# Polarshield_v2_3.net
KiCad netlist of a schematic drawn in EAGLE
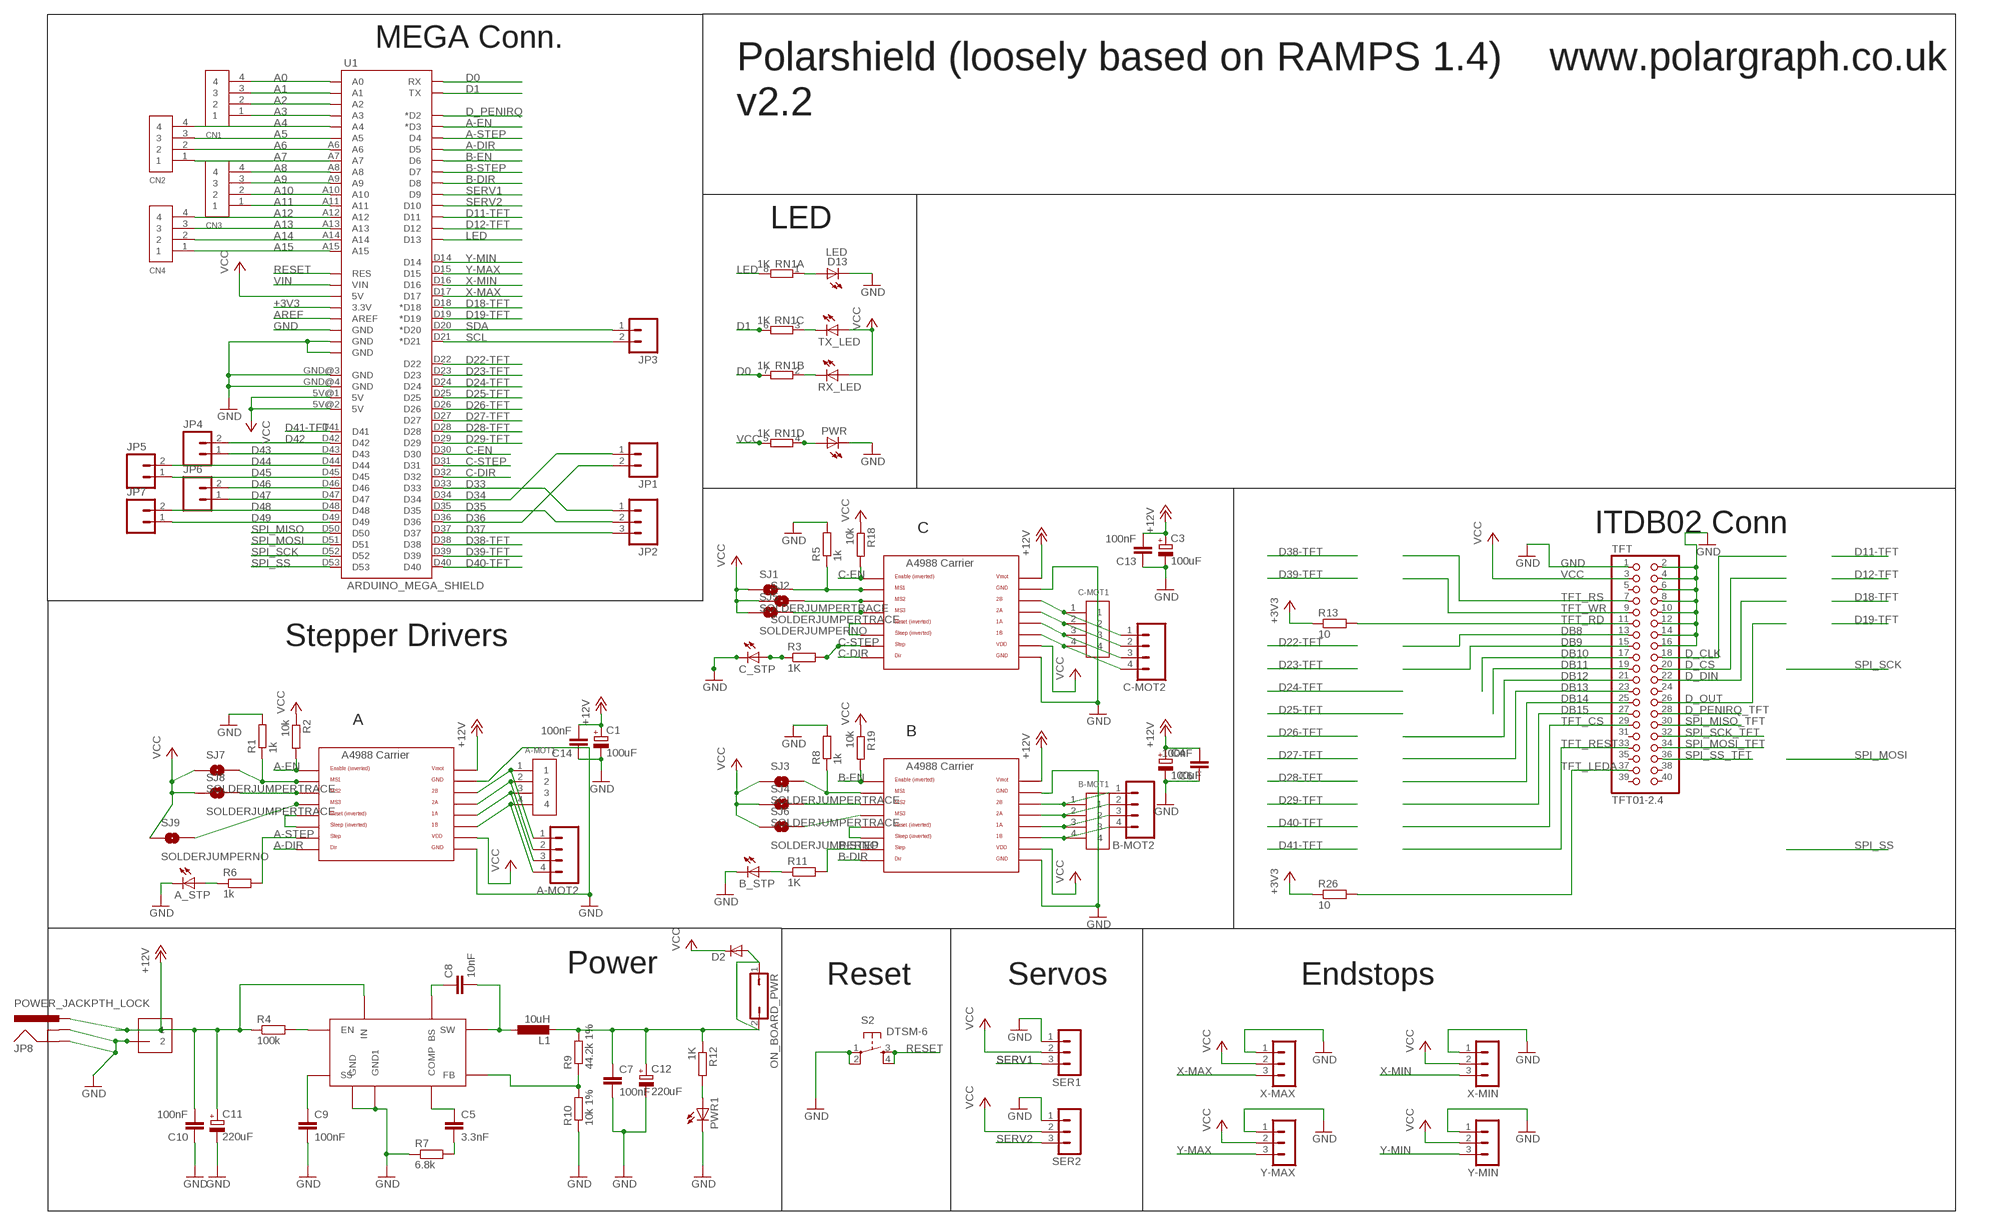
[diagram p0: schematic, sheet 1, part 1 of 2]
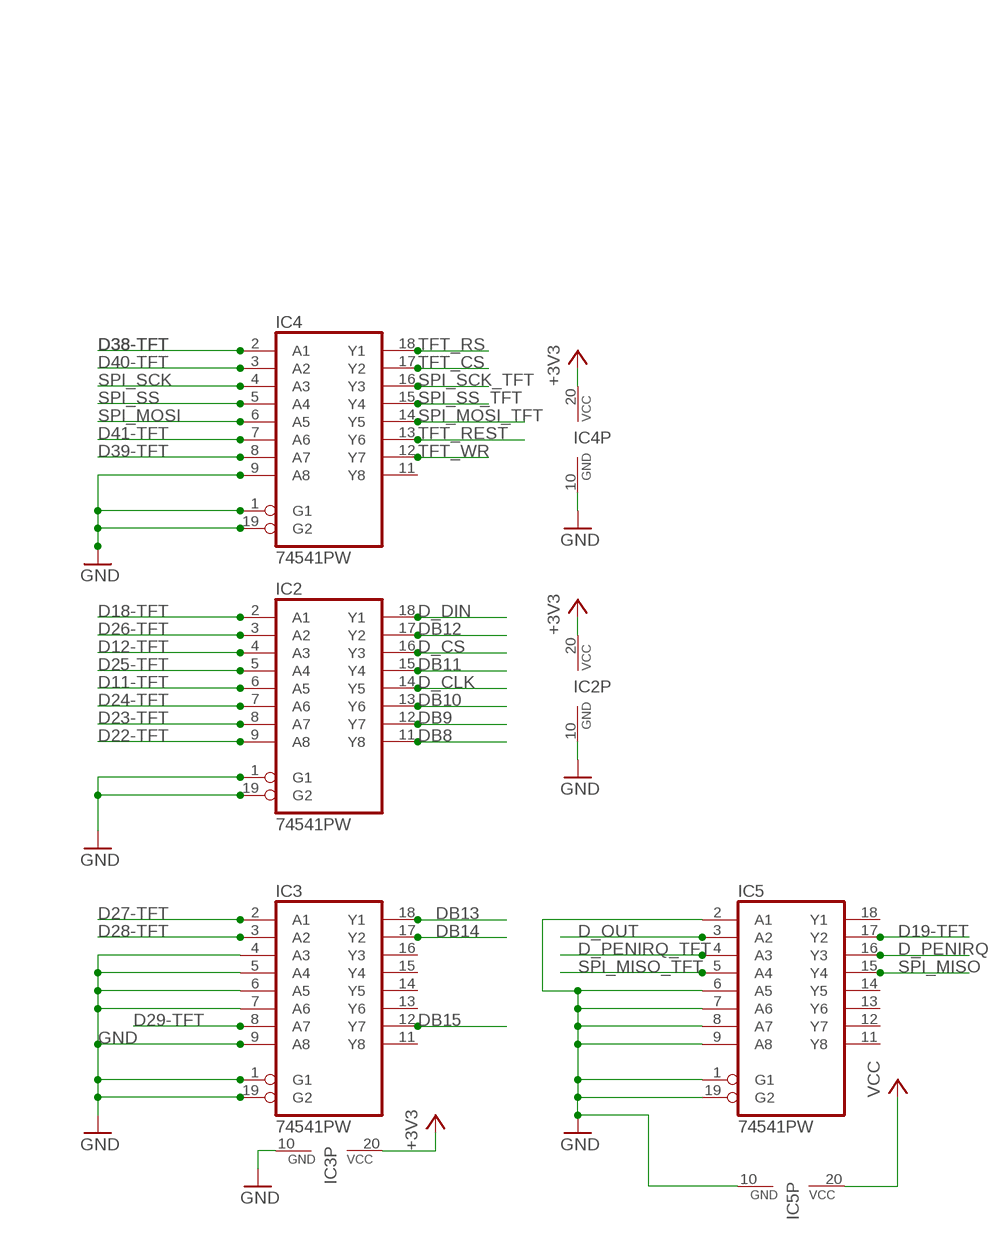
[diagram p1: schematic, sheet 1, part 2 of 2]

(export (version "E")
  (design (tool "Eeschema 10.0.6"))
  (components
    (comp (ref "A-MOT1")
      (value "1X4-BIG")
      (footprint "eagle-import:1X04-BIG")
      (libsource (lib "eagle-import") (part "adafruit_1X4-BIG"))
    )
    (comp (ref "A-MOT2")
      (value "M04SCREW")
      (footprint "eagle-import:SCREWTERMINAL-3.5MM-4")
      (libsource (lib "eagle-import") (part "M04SCREW"))
    )
    (comp (ref "A_STP")
      (value "LEDCHIP-LED0805")
      (footprint "eagle-import:CHIP-LED0805")
      (libsource (lib "eagle-import") (part "LEDCHIP-LED0805"))
    )
    (comp (ref "B-MOT1")
      (value "1X4-BIG")
      (footprint "eagle-import:1X04-BIG")
      (libsource (lib "eagle-import") (part "adafruit_1X4-BIG"))
    )
    (comp (ref "B-MOT2")
      (value "M04SCREW")
      (footprint "eagle-import:SCREWTERMINAL-3.5MM-4")
      (libsource (lib "eagle-import") (part "M04SCREW"))
    )
    (comp (ref "B_STP")
      (value "LEDCHIP-LED0805")
      (footprint "eagle-import:CHIP-LED0805")
      (libsource (lib "eagle-import") (part "LEDCHIP-LED0805"))
    )
    (comp (ref "C-MOT1")
      (value "1X4-BIG")
      (footprint "eagle-import:1X04-BIG")
      (libsource (lib "eagle-import") (part "adafruit_1X4-BIG"))
    )
    (comp (ref "C-MOT2")
      (value "M04SCREW")
      (footprint "eagle-import:SCREWTERMINAL-3.5MM-4")
      (libsource (lib "eagle-import") (part "M04SCREW"))
    )
    (comp (ref "C1")
      (value "100uF")
      (footprint "eagle-import:153CLV-0605")
      (libsource (lib "eagle-import") (part "CPOL-EU153CLV-0605"))
    )
    (comp (ref "C3")
      (value "100uF")
      (footprint "eagle-import:153CLV-0605")
      (libsource (lib "eagle-import") (part "CPOL-EU153CLV-0605"))
    )
    (comp (ref "C4")
      (value "100uF")
      (footprint "eagle-import:153CLV-0605")
      (libsource (lib "eagle-import") (part "CPOL-EU153CLV-0605"))
    )
    (comp (ref "C5")
      (value "3.3nF")
      (footprint "eagle-import:C0805K")
      (libsource (lib "eagle-import") (part "C-EUC0805K"))
    )
    (comp (ref "C6")
      (value "100nF")
      (footprint "eagle-import:C0805")
      (libsource (lib "eagle-import") (part "C-EUC0805"))
    )
    (comp (ref "C7")
      (value "100nF")
      (footprint "eagle-import:C0805K")
      (libsource (lib "eagle-import") (part "C-EUC0805K"))
    )
    (comp (ref "C8")
      (value "10nF")
      (footprint "eagle-import:C0805K")
      (libsource (lib "eagle-import") (part "C-EUC0805K"))
    )
    (comp (ref "C9")
      (value "100nF")
      (footprint "eagle-import:C0805K")
      (libsource (lib "eagle-import") (part "C-EUC0805K"))
    )
    (comp (ref "C10")
      (value "100nF")
      (footprint "eagle-import:C0805K")
      (libsource (lib "eagle-import") (part "C-EUC0805K"))
    )
    (comp (ref "C11")
      (value "220uF")
      (footprint "eagle-import:153CLV-0807")
      (libsource (lib "eagle-import") (part "resistor_CPOL-EU153CLV-0807"))
    )
    (comp (ref "C12")
      (value "220uF")
      (footprint "eagle-import:153CLV-0807")
      (libsource (lib "eagle-import") (part "resistor_CPOL-EU153CLV-0807"))
    )
    (comp (ref "C13")
      (value "100nF")
      (footprint "eagle-import:C0805")
      (libsource (lib "eagle-import") (part "C-EUC0805"))
    )
    (comp (ref "C14")
      (value "100nF")
      (footprint "eagle-import:C0805")
      (libsource (lib "eagle-import") (part "C-EUC0805"))
    )
    (comp (ref "CN1")
      (value "1X4-CLEANBIG")
      (footprint "eagle-import:1X04-CLEANBIG")
      (libsource (lib "eagle-import") (part "1X4-CLEANBIG"))
    )
    (comp (ref "CN2")
      (value "1X4-CLEANBIG")
      (footprint "eagle-import:1X04-CLEANBIG")
      (libsource (lib "eagle-import") (part "1X4-CLEANBIG"))
    )
    (comp (ref "CN3")
      (value "1X4-CLEANBIG")
      (footprint "eagle-import:1X04-CLEANBIG")
      (libsource (lib "eagle-import") (part "1X4-CLEANBIG"))
    )
    (comp (ref "CN4")
      (value "1X4-CLEANBIG")
      (footprint "eagle-import:1X04-CLEANBIG")
      (libsource (lib "eagle-import") (part "1X4-CLEANBIG"))
    )
    (comp (ref "C_STP")
      (value "LEDCHIP-LED0805")
      (footprint "eagle-import:CHIP-LED0805")
      (libsource (lib "eagle-import") (part "LEDCHIP-LED0805"))
    )
    (comp (ref "D2")
      (value "DIODE-DO214BA")
      (footprint "eagle-import:DO214BA")
      (libsource (lib "eagle-import") (part "DIODE-DO214BA"))
    )
    (comp (ref "D13")
      (value "LED")
      (footprint "eagle-import:CHIP-LED0805")
      (libsource (lib "eagle-import") (part "LEDCHIP-LED0805"))
    )
    (comp (ref "IC1")
      (value "MP2307")
      (footprint "eagle-import:SOIC8")
      (libsource (lib "eagle-import") (part "MP2307"))
    )
    (comp (ref "IC2")
      (value "74541PW")
      (footprint "eagle-import:TSSOP20")
      (libsource (lib "eagle-import") (part "74541PW"))
    )
    (comp (ref "IC3")
      (value "74541PW")
      (footprint "eagle-import:TSSOP20")
      (libsource (lib "eagle-import") (part "74541PW"))
    )
    (comp (ref "IC4")
      (value "74541PW")
      (footprint "eagle-import:TSSOP20")
      (libsource (lib "eagle-import") (part "74541PW"))
    )
    (comp (ref "IC5")
      (value "74541PW")
      (footprint "eagle-import:TSSOP20")
      (libsource (lib "eagle-import") (part "74541PW"))
    )
    (comp (ref "J1")
      (value "1X2-3.5MM")
      (footprint "eagle-import:1X2-3.5MM")
      (libsource (lib "eagle-import") (part "1X2-3.5MM"))
    )
    (comp (ref "JP1")
      (value "M021X02_NO_SILK")
      (footprint "eagle-import:1X02_NO_SILK")
      (libsource (lib "eagle-import") (part "M021X02_NO_SILK"))
    )
    (comp (ref "JP2")
      (value "M031X03_NO_SILK")
      (footprint "eagle-import:1X03_NO_SILK")
      (libsource (lib "eagle-import") (part "M031X03_NO_SILK"))
    )
    (comp (ref "JP3")
      (value "M021X02_NO_SILK")
      (footprint "eagle-import:1X02_NO_SILK")
      (libsource (lib "eagle-import") (part "M021X02_NO_SILK"))
    )
    (comp (ref "JP4")
      (value "M021X02_NO_SILK")
      (footprint "eagle-import:1X02_NO_SILK")
      (libsource (lib "eagle-import") (part "M021X02_NO_SILK"))
    )
    (comp (ref "JP5")
      (value "M021X02_NO_SILK")
      (footprint "eagle-import:1X02_NO_SILK")
      (libsource (lib "eagle-import") (part "M021X02_NO_SILK"))
    )
    (comp (ref "JP6")
      (value "M021X02_NO_SILK")
      (footprint "eagle-import:1X02_NO_SILK")
      (libsource (lib "eagle-import") (part "M021X02_NO_SILK"))
    )
    (comp (ref "JP7")
      (value "M021X02_NO_SILK")
      (footprint "eagle-import:1X02_NO_SILK")
      (libsource (lib "eagle-import") (part "M021X02_NO_SILK"))
    )
    (comp (ref "JP8")
      (value "POWER_JACKPTH_LOCK")
      (footprint "eagle-import:POWER_JACK_PTH_LOCK")
      (libsource (lib "eagle-import") (part "POWER_JACKPTH_LOCK"))
    )
    (comp (ref "L1")
      (value "10uH")
      (footprint "eagle-import:PIS2816")
      (libsource (lib "eagle-import") (part "L-EUPIS2816"))
    )
    (comp (ref "ON_BOARD_PWR")
      (value "JP1Q")
      (footprint "eagle-import:JP1")
      (libsource (lib "eagle-import") (part "JP1Q"))
    )
    (comp (ref "PWR")
      (value "LEDCHIP-LED0805")
      (footprint "eagle-import:CHIP-LED0805")
      (libsource (lib "eagle-import") (part "LEDCHIP-LED0805"))
    )
    (comp (ref "PWR1")
      (value "LEDCHIP-LED0805")
      (footprint "eagle-import:CHIP-LED0805")
      (libsource (lib "eagle-import") (part "LEDCHIP-LED0805"))
    )
    (comp (ref "R1")
      (value "1k")
      (footprint "eagle-import:R0805")
      (libsource (lib "eagle-import") (part "R-EU_R0805"))
    )
    (comp (ref "R2")
      (value "10k")
      (footprint "eagle-import:R0805")
      (libsource (lib "eagle-import") (part "R-EU_R0805"))
    )
    (comp (ref "R3")
      (value "1K")
      (footprint "eagle-import:R0805")
      (libsource (lib "eagle-import") (part "R-EU_R0805"))
    )
    (comp (ref "R4")
      (value "100k")
      (footprint "eagle-import:R0805")
      (libsource (lib "eagle-import") (part "resistor_R-EU_R0805"))
    )
    (comp (ref "R5")
      (value "1k")
      (footprint "eagle-import:R0805")
      (libsource (lib "eagle-import") (part "R-EU_R0805"))
    )
    (comp (ref "R6")
      (value "1k")
      (footprint "eagle-import:R0805")
      (libsource (lib "eagle-import") (part "R-EU_R0805"))
    )
    (comp (ref "R7")
      (value "6.8k")
      (footprint "eagle-import:R0805")
      (libsource (lib "eagle-import") (part "resistor_R-EU_R0805"))
    )
    (comp (ref "R8")
      (value "1k")
      (footprint "eagle-import:R0805")
      (libsource (lib "eagle-import") (part "R-EU_R0805"))
    )
    (comp (ref "R9")
      (value "44.2k 1%")
      (footprint "eagle-import:R0805")
      (libsource (lib "eagle-import") (part "resistor_R-EU_R0805"))
    )
    (comp (ref "R10")
      (value "10k 1%")
      (footprint "eagle-import:R0805")
      (libsource (lib "eagle-import") (part "resistor_R-EU_R0805"))
    )
    (comp (ref "R11")
      (value "1K")
      (footprint "eagle-import:R0805")
      (libsource (lib "eagle-import") (part "R-EU_R0805"))
    )
    (comp (ref "R12")
      (value "1K")
      (footprint "eagle-import:R0805")
      (libsource (lib "eagle-import") (part "R-EU_R0805"))
    )
    (comp (ref "R13")
      (value "10")
      (footprint "eagle-import:R0805")
      (libsource (lib "eagle-import") (part "resistor_R-EU_R0805"))
    )
    (comp (ref "R18")
      (value "10k")
      (footprint "eagle-import:R0805")
      (libsource (lib "eagle-import") (part "R-EU_R0805"))
    )
    (comp (ref "R19")
      (value "10k")
      (footprint "eagle-import:R0805")
      (libsource (lib "eagle-import") (part "R-EU_R0805"))
    )
    (comp (ref "R26")
      (value "10")
      (footprint "eagle-import:R0805")
      (libsource (lib "eagle-import") (part "resistor_R-EU_R0805"))
    )
    (comp (ref "RN1")
      (value "1K")
      (footprint "eagle-import:EXBS8V")
      (libsource (lib "eagle-import") (part "4R-NEXBS8V"))
    )
    (comp (ref "RX_LED")
      (value "LEDCHIP-LED0805")
      (footprint "eagle-import:CHIP-LED0805")
      (libsource (lib "eagle-import") (part "LEDCHIP-LED0805"))
    )
    (comp (ref "S2")
      (value "DTSM-6")
      (footprint "eagle-import:DTSM-6")
      (libsource (lib "eagle-import") (part "DTSM-6"))
    )
    (comp (ref "SER1")
      (value "3PIN-HEADER")
      (footprint "eagle-import:3PIN-HEADER")
      (libsource (lib "eagle-import") (part "3PIN-HEADER"))
    )
    (comp (ref "SER2")
      (value "3PIN-HEADER")
      (footprint "eagle-import:3PIN-HEADER")
      (libsource (lib "eagle-import") (part "3PIN-HEADER"))
    )
    (comp (ref "SJ1")
      (value "SOLDERJUMPERTRACE")
      (footprint "eagle-import:SJ_2S-TRACE")
      (libsource (lib "eagle-import") (part "SOLDERJUMPERTRACE"))
    )
    (comp (ref "SJ2")
      (value "SOLDERJUMPERTRACE")
      (footprint "eagle-import:SJ_2S-TRACE")
      (libsource (lib "eagle-import") (part "SOLDERJUMPERTRACE"))
    )
    (comp (ref "SJ3")
      (value "SOLDERJUMPERTRACE")
      (footprint "eagle-import:SJ_2S-TRACE")
      (libsource (lib "eagle-import") (part "SOLDERJUMPERTRACE"))
    )
    (comp (ref "SJ4")
      (value "SOLDERJUMPERTRACE")
      (footprint "eagle-import:SJ_2S-TRACE")
      (libsource (lib "eagle-import") (part "SOLDERJUMPERTRACE"))
    )
    (comp (ref "SJ5")
      (value "SOLDERJUMPERNO")
      (footprint "eagle-import:SJ_2S-NO")
      (libsource (lib "eagle-import") (part "SOLDERJUMPERNO"))
    )
    (comp (ref "SJ6")
      (value "SOLDERJUMPERNO")
      (footprint "eagle-import:SJ_2S-NO")
      (libsource (lib "eagle-import") (part "SOLDERJUMPERNO"))
    )
    (comp (ref "SJ7")
      (value "SOLDERJUMPERTRACE")
      (footprint "eagle-import:SJ_2S-TRACE")
      (libsource (lib "eagle-import") (part "SOLDERJUMPERTRACE"))
    )
    (comp (ref "SJ8")
      (value "SOLDERJUMPERTRACE")
      (footprint "eagle-import:SJ_2S-TRACE")
      (libsource (lib "eagle-import") (part "SOLDERJUMPERTRACE"))
    )
    (comp (ref "SJ9")
      (value "SOLDERJUMPERNO")
      (footprint "eagle-import:SJ_2S-NO")
      (libsource (lib "eagle-import") (part "SOLDERJUMPERNO"))
    )
    (comp (ref "TFT")
      (value "TFT01-2.4")
      (footprint "eagle-import:TFT01-2.4")
      (libsource (lib "eagle-import") (part "TFT01-2.4"))
    )
    (comp (ref "TX_LED")
      (value "LEDCHIP-LED0805")
      (footprint "eagle-import:CHIP-LED0805")
      (libsource (lib "eagle-import") (part "LEDCHIP-LED0805"))
    )
    (comp (ref "U$1")
      (value "A4988BREAKOUT")
      (footprint "eagle-import:A4988BREAKOUT")
      (libsource (lib "eagle-import") (part "A4988BREAKOUT"))
    )
    (comp (ref "U$6")
      (value "A4988BREAKOUT")
      (footprint "eagle-import:A4988BREAKOUT")
      (libsource (lib "eagle-import") (part "A4988BREAKOUT"))
    )
    (comp (ref "U$7")
      (value "A4988BREAKOUT")
      (footprint "eagle-import:A4988BREAKOUT")
      (libsource (lib "eagle-import") (part "A4988BREAKOUT"))
    )
    (comp (ref "U1")
      (value "ARDUINO_MEGA_SHIELD")
      (footprint "eagle-import:ARDUINO_MEGA_SHIELD")
      (libsource (lib "eagle-import") (part "ARDUINO_MEGA_SHIELD"))
    )
    (comp (ref "X-MAX")
      (value "3PIN-HEADER")
      (footprint "eagle-import:3PIN-HEADER")
      (libsource (lib "eagle-import") (part "3PIN-HEADER"))
    )
    (comp (ref "X-MIN")
      (value "3PIN-HEADER")
      (footprint "eagle-import:3PIN-HEADER")
      (libsource (lib "eagle-import") (part "3PIN-HEADER"))
    )
    (comp (ref "Y-MAX")
      (value "3PIN-HEADER")
      (footprint "eagle-import:3PIN-HEADER")
      (libsource (lib "eagle-import") (part "3PIN-HEADER"))
    )
    (comp (ref "Y-MIN")
      (value "3PIN-HEADER")
      (footprint "eagle-import:3PIN-HEADER")
      (libsource (lib "eagle-import") (part "3PIN-HEADER"))
    )
  )
  (nets
    (net (code "1") (name "+3V3") (class "Default")
      (node (ref "IC2") (pin "20") (pinfunction "VCC_20") (pintype "power_in"))
      (node (ref "IC3") (pin "20") (pinfunction "VCC_20") (pintype "power_in"))
      (node (ref "IC4") (pin "20") (pinfunction "VCC_20") (pintype "power_in"))
      (node (ref "R13") (pin "1") (pinfunction "1_1") (pintype "passive"))
      (node (ref "R26") (pin "1") (pinfunction "1_1") (pintype "passive"))
      (node (ref "U1") (pin "3.3V") (pinfunction "3.3V_3.3V") (pintype "bidirectional"))
    )
    (net (code "2") (name "+12V") (class "Default")
      (node (ref "C1") (pin "+") (pinfunction "+_+") (pintype "passive"))
      (node (ref "C10") (pin "2") (pinfunction "2_2") (pintype "passive"))
      (node (ref "C11") (pin "+") (pinfunction "+_+") (pintype "passive"))
      (node (ref "C13") (pin "2") (pinfunction "2_2") (pintype "passive"))
      (node (ref "C14") (pin "2") (pinfunction "2_2") (pintype "passive"))
      (node (ref "C3") (pin "+") (pinfunction "+_+") (pintype "passive"))
      (node (ref "C4") (pin "+") (pinfunction "+_+") (pintype "passive"))
      (node (ref "C6") (pin "2") (pinfunction "2_2") (pintype "passive"))
      (node (ref "IC1") (pin "IN") (pinfunction "IN_IN") (pintype "bidirectional"))
      (node (ref "J1") (pin "1") (pinfunction "1_1") (pintype "passive"))
      (node (ref "JP8") (pin "PWR") (pinfunction "PWR_PWR") (pintype "bidirectional"))
      (node (ref "R4") (pin "1") (pinfunction "1_1") (pintype "passive"))
      (node (ref "U$1") (pin "VMOT") (pinfunction "VMOT_VMOT") (pintype "power_in"))
      (node (ref "U$6") (pin "VMOT") (pinfunction "VMOT_VMOT") (pintype "power_in"))
      (node (ref "U$7") (pin "VMOT") (pinfunction "VMOT_VMOT") (pintype "power_in"))
    )
    (net (code "3") (name "/A-DIR") (class "Default")
      (node (ref "U$1") (pin "DIR") (pinfunction "DIR_DIR") (pintype "input"))
      (node (ref "U1") (pin "D5") (pinfunction "D5_D5") (pintype "bidirectional"))
    )
    (net (code "4") (name "/A-EN") (class "Default")
      (node (ref "R2") (pin "2") (pinfunction "2_2") (pintype "passive"))
      (node (ref "U$1") (pin "EN") (pinfunction "EN_EN") (pintype "input"))
      (node (ref "U1") (pin "D3") (pinfunction "*D3_D3") (pintype "bidirectional"))
    )
    (net (code "5") (name "/A-STEP") (class "Default")
      (node (ref "R6") (pin "2") (pinfunction "2_2") (pintype "passive"))
      (node (ref "U$1") (pin "STEP") (pinfunction "STEP_STEP") (pintype "input"))
      (node (ref "U1") (pin "D4") (pinfunction "D4_D4") (pintype "bidirectional"))
    )
    (net (code "6") (name "/A0") (class "Default")
      (node (ref "CN1") (pin "4") (pinfunction "4_4") (pintype "bidirectional"))
      (node (ref "U1") (pin "A0") (pinfunction "A0_A0") (pintype "bidirectional"))
    )
    (net (code "7") (name "/A1") (class "Default")
      (node (ref "CN1") (pin "3") (pinfunction "3_3") (pintype "bidirectional"))
      (node (ref "U1") (pin "A1") (pinfunction "A1_A1") (pintype "bidirectional"))
    )
    (net (code "8") (name "/A2") (class "Default")
      (node (ref "CN1") (pin "2") (pinfunction "2_2") (pintype "bidirectional"))
      (node (ref "U1") (pin "A2") (pinfunction "A2_A2") (pintype "bidirectional"))
    )
    (net (code "9") (name "/A3") (class "Default")
      (node (ref "CN1") (pin "1") (pinfunction "1_1") (pintype "bidirectional"))
      (node (ref "U1") (pin "A3") (pinfunction "A3_A3") (pintype "bidirectional"))
    )
    (net (code "10") (name "/A4") (class "Default")
      (node (ref "CN2") (pin "4") (pinfunction "4_4") (pintype "bidirectional"))
      (node (ref "U1") (pin "A4") (pinfunction "A4_A4") (pintype "bidirectional"))
    )
    (net (code "11") (name "/A5") (class "Default")
      (node (ref "CN2") (pin "3") (pinfunction "3_3") (pintype "bidirectional"))
      (node (ref "U1") (pin "A5") (pinfunction "A5_A5") (pintype "bidirectional"))
    )
    (net (code "12") (name "/A6") (class "Default")
      (node (ref "CN2") (pin "2") (pinfunction "2_2") (pintype "bidirectional"))
      (node (ref "U1") (pin "A6") (pinfunction "A6_A6") (pintype "bidirectional"))
    )
    (net (code "13") (name "/A7") (class "Default")
      (node (ref "CN2") (pin "1") (pinfunction "1_1") (pintype "bidirectional"))
      (node (ref "U1") (pin "A7") (pinfunction "A7_A7") (pintype "bidirectional"))
    )
    (net (code "14") (name "/A8") (class "Default")
      (node (ref "CN3") (pin "4") (pinfunction "4_4") (pintype "bidirectional"))
      (node (ref "U1") (pin "A8") (pinfunction "A8_A8") (pintype "bidirectional"))
    )
    (net (code "15") (name "/A9") (class "Default")
      (node (ref "CN3") (pin "3") (pinfunction "3_3") (pintype "bidirectional"))
      (node (ref "U1") (pin "A9") (pinfunction "A9_A9") (pintype "bidirectional"))
    )
    (net (code "16") (name "/A10") (class "Default")
      (node (ref "CN3") (pin "2") (pinfunction "2_2") (pintype "bidirectional"))
      (node (ref "U1") (pin "A10") (pinfunction "A10_A10") (pintype "bidirectional"))
    )
    (net (code "17") (name "/A11") (class "Default")
      (node (ref "CN3") (pin "1") (pinfunction "1_1") (pintype "bidirectional"))
      (node (ref "U1") (pin "A11") (pinfunction "A11_A11") (pintype "bidirectional"))
    )
    (net (code "18") (name "/A12") (class "Default")
      (node (ref "CN4") (pin "4") (pinfunction "4_4") (pintype "bidirectional"))
      (node (ref "U1") (pin "A12") (pinfunction "A12_A12") (pintype "bidirectional"))
    )
    (net (code "19") (name "/A13") (class "Default")
      (node (ref "CN4") (pin "3") (pinfunction "3_3") (pintype "bidirectional"))
      (node (ref "U1") (pin "A13") (pinfunction "A13_A13") (pintype "bidirectional"))
    )
    (net (code "20") (name "/A14") (class "Default")
      (node (ref "CN4") (pin "2") (pinfunction "2_2") (pintype "bidirectional"))
      (node (ref "U1") (pin "A14") (pinfunction "A14_A14") (pintype "bidirectional"))
    )
    (net (code "21") (name "/A15") (class "Default")
      (node (ref "CN4") (pin "1") (pinfunction "1_1") (pintype "bidirectional"))
      (node (ref "U1") (pin "A15") (pinfunction "A15_A15") (pintype "bidirectional"))
    )
    (net (code "22") (name "/AREF") (class "Default")
      (node (ref "U1") (pin "AREF") (pinfunction "AREF_AREF") (pintype "bidirectional"))
    )
    (net (code "23") (name "/B-DIR") (class "Default")
      (node (ref "U$7") (pin "DIR") (pinfunction "DIR_DIR") (pintype "input"))
      (node (ref "U1") (pin "D8") (pinfunction "D8_D8") (pintype "bidirectional"))
    )
    (net (code "24") (name "/B-EN") (class "Default")
      (node (ref "R19") (pin "2") (pinfunction "2_2") (pintype "passive"))
      (node (ref "U$7") (pin "EN") (pinfunction "EN_EN") (pintype "input"))
      (node (ref "U1") (pin "D6") (pinfunction "D6_D6") (pintype "bidirectional"))
    )
    (net (code "25") (name "/B-STEP") (class "Default")
      (node (ref "R11") (pin "2") (pinfunction "2_2") (pintype "passive"))
      (node (ref "U$7") (pin "STEP") (pinfunction "STEP_STEP") (pintype "input"))
      (node (ref "U1") (pin "D7") (pinfunction "D7_D7") (pintype "bidirectional"))
    )
    (net (code "26") (name "/C-DIR") (class "Default")
      (node (ref "U$6") (pin "DIR") (pinfunction "DIR_DIR") (pintype "input"))
      (node (ref "U1") (pin "D32") (pinfunction "D32_D32") (pintype "bidirectional"))
    )
    (net (code "27") (name "/C-EN") (class "Default")
      (node (ref "R18") (pin "2") (pinfunction "2_2") (pintype "passive"))
      (node (ref "U$6") (pin "EN") (pinfunction "EN_EN") (pintype "input"))
      (node (ref "U1") (pin "D30") (pinfunction "D30_D30") (pintype "bidirectional"))
    )
    (net (code "28") (name "/C-STEP") (class "Default")
      (node (ref "R3") (pin "2") (pinfunction "2_2") (pintype "passive"))
      (node (ref "U$6") (pin "STEP") (pinfunction "STEP_STEP") (pintype "input"))
      (node (ref "U1") (pin "D31") (pinfunction "D31_D31") (pintype "bidirectional"))
    )
    (net (code "29") (name "/D0") (class "Default")
      (node (ref "RN1") (pin "7") (pinfunction "2_7") (pintype "passive"))
      (node (ref "U1") (pin "RX") (pinfunction "RX_RX") (pintype "bidirectional"))
    )
    (net (code "30") (name "/D1") (class "Default")
      (node (ref "RN1") (pin "6") (pinfunction "2_6") (pintype "passive"))
      (node (ref "U1") (pin "TX") (pinfunction "TX_TX") (pintype "bidirectional"))
    )
    (net (code "31") (name "/D11-TFT") (class "Default")
      (node (ref "IC2") (pin "6") (pinfunction "A5_6") (pintype "input"))
      (node (ref "U1") (pin "D11") (pinfunction "D11_D11") (pintype "bidirectional"))
    )
    (net (code "32") (name "/D12-TFT") (class "Default")
      (node (ref "IC2") (pin "4") (pinfunction "A3_4") (pintype "input"))
      (node (ref "U1") (pin "D12") (pinfunction "D12_D12") (pintype "bidirectional"))
    )
    (net (code "33") (name "/D18-TFT") (class "Default")
      (node (ref "IC2") (pin "2") (pinfunction "A1_2") (pintype "input"))
      (node (ref "U1") (pin "D18") (pinfunction "*D18_D18") (pintype "bidirectional"))
    )
    (net (code "34") (name "/D19-TFT") (class "Default")
      (node (ref "IC5") (pin "17") (pinfunction "Y2_17") (pintype "tri_state"))
      (node (ref "U1") (pin "D19") (pinfunction "*D19_D19") (pintype "bidirectional"))
    )
    (net (code "35") (name "/D22-TFT") (class "Default")
      (node (ref "IC2") (pin "9") (pinfunction "A8_9") (pintype "input"))
      (node (ref "U1") (pin "D22") (pinfunction "D22_D22") (pintype "bidirectional"))
    )
    (net (code "36") (name "/D23-TFT") (class "Default")
      (node (ref "IC2") (pin "8") (pinfunction "A7_8") (pintype "input"))
      (node (ref "U1") (pin "D23") (pinfunction "D23_D23") (pintype "bidirectional"))
    )
    (net (code "37") (name "/D24-TFT") (class "Default")
      (node (ref "IC2") (pin "7") (pinfunction "A6_7") (pintype "input"))
      (node (ref "U1") (pin "D24") (pinfunction "D24_D24") (pintype "bidirectional"))
    )
    (net (code "38") (name "/D25-TFT") (class "Default")
      (node (ref "IC2") (pin "5") (pinfunction "A4_5") (pintype "input"))
      (node (ref "U1") (pin "D25") (pinfunction "D25_D25") (pintype "bidirectional"))
    )
    (net (code "39") (name "/D26-TFT") (class "Default")
      (node (ref "IC2") (pin "3") (pinfunction "A2_3") (pintype "input"))
      (node (ref "U1") (pin "D26") (pinfunction "D26_D26") (pintype "bidirectional"))
    )
    (net (code "40") (name "/D27-TFT") (class "Default")
      (node (ref "IC3") (pin "2") (pinfunction "A1_2") (pintype "input"))
      (node (ref "U1") (pin "D27") (pinfunction "D27_D27") (pintype "bidirectional"))
    )
    (net (code "41") (name "/D28-TFT") (class "Default")
      (node (ref "IC3") (pin "3") (pinfunction "A2_3") (pintype "input"))
      (node (ref "U1") (pin "D28") (pinfunction "D28_D28") (pintype "bidirectional"))
    )
    (net (code "42") (name "/D29-TFT") (class "Default")
      (node (ref "IC3") (pin "8") (pinfunction "A7_8") (pintype "input"))
      (node (ref "U1") (pin "D29") (pinfunction "D29_D29") (pintype "bidirectional"))
    )
    (net (code "43") (name "/D33") (class "Default")
      (node (ref "JP2") (pin "1") (pinfunction "1_1") (pintype "passive"))
      (node (ref "U1") (pin "D33") (pinfunction "D33_D33") (pintype "bidirectional"))
    )
    (net (code "44") (name "/D34") (class "Default")
      (node (ref "JP1") (pin "1") (pinfunction "1_1") (pintype "passive"))
      (node (ref "U1") (pin "D34") (pinfunction "D34_D34") (pintype "bidirectional"))
    )
    (net (code "45") (name "/D35") (class "Default")
      (node (ref "JP2") (pin "2") (pinfunction "2_2") (pintype "passive"))
      (node (ref "U1") (pin "D35") (pinfunction "D35_D35") (pintype "bidirectional"))
    )
    (net (code "46") (name "/D36") (class "Default")
      (node (ref "JP1") (pin "2") (pinfunction "2_2") (pintype "passive"))
      (node (ref "U1") (pin "D36") (pinfunction "D36_D36") (pintype "bidirectional"))
    )
    (net (code "47") (name "/D37") (class "Default")
      (node (ref "JP2") (pin "3") (pinfunction "3_3") (pintype "passive"))
      (node (ref "U1") (pin "D37") (pinfunction "D37_D37") (pintype "bidirectional"))
    )
    (net (code "48") (name "/D38-TFT") (class "Default")
      (node (ref "IC4") (pin "2") (pinfunction "A1_2") (pintype "input"))
      (node (ref "U1") (pin "D38") (pinfunction "D38_D38") (pintype "bidirectional"))
    )
    (net (code "49") (name "/D39-TFT") (class "Default")
      (node (ref "IC4") (pin "8") (pinfunction "A7_8") (pintype "input"))
      (node (ref "U1") (pin "D39") (pinfunction "D39_D39") (pintype "bidirectional"))
    )
    (net (code "50") (name "/D40-TFT") (class "Default")
      (node (ref "IC4") (pin "3") (pinfunction "A2_3") (pintype "input"))
      (node (ref "U1") (pin "D40") (pinfunction "D40_D40") (pintype "bidirectional"))
    )
    (net (code "51") (name "/D41-TFT") (class "Default")
      (node (ref "IC4") (pin "7") (pinfunction "A6_7") (pintype "input"))
      (node (ref "U1") (pin "D41") (pinfunction "D41_D41") (pintype "bidirectional"))
    )
    (net (code "52") (name "/D42") (class "Default")
      (node (ref "JP4") (pin "2") (pinfunction "2_2") (pintype "passive"))
      (node (ref "U1") (pin "D42") (pinfunction "D42_D42") (pintype "bidirectional"))
    )
    (net (code "53") (name "/D43") (class "Default")
      (node (ref "JP4") (pin "1") (pinfunction "1_1") (pintype "passive"))
      (node (ref "U1") (pin "D43") (pinfunction "D43_D43") (pintype "bidirectional"))
    )
    (net (code "54") (name "/D44") (class "Default")
      (node (ref "JP5") (pin "2") (pinfunction "2_2") (pintype "passive"))
      (node (ref "U1") (pin "D44") (pinfunction "D44_D44") (pintype "bidirectional"))
    )
    (net (code "55") (name "/D45") (class "Default")
      (node (ref "JP5") (pin "1") (pinfunction "1_1") (pintype "passive"))
      (node (ref "U1") (pin "D45") (pinfunction "D45_D45") (pintype "bidirectional"))
    )
    (net (code "56") (name "/D46") (class "Default")
      (node (ref "JP6") (pin "2") (pinfunction "2_2") (pintype "passive"))
      (node (ref "U1") (pin "D46") (pinfunction "D46_D46") (pintype "bidirectional"))
    )
    (net (code "57") (name "/D47") (class "Default")
      (node (ref "JP6") (pin "1") (pinfunction "1_1") (pintype "passive"))
      (node (ref "U1") (pin "D47") (pinfunction "D47_D47") (pintype "bidirectional"))
    )
    (net (code "58") (name "/D48") (class "Default")
      (node (ref "JP7") (pin "2") (pinfunction "2_2") (pintype "passive"))
      (node (ref "U1") (pin "D48") (pinfunction "D48_D48") (pintype "bidirectional"))
    )
    (net (code "59") (name "/D49") (class "Default")
      (node (ref "JP7") (pin "1") (pinfunction "1_1") (pintype "passive"))
      (node (ref "U1") (pin "D49") (pinfunction "D49_D49") (pintype "bidirectional"))
    )
    (net (code "60") (name "/DB8") (class "Default")
      (node (ref "IC2") (pin "11") (pinfunction "Y8_11") (pintype "tri_state"))
      (node (ref "TFT") (pin "13") (pinfunction "13_13") (pintype "passive"))
    )
    (net (code "61") (name "/DB9") (class "Default")
      (node (ref "IC2") (pin "12") (pinfunction "Y7_12") (pintype "tri_state"))
      (node (ref "TFT") (pin "15") (pinfunction "15_15") (pintype "passive"))
    )
    (net (code "62") (name "/DB10") (class "Default")
      (node (ref "IC2") (pin "13") (pinfunction "Y6_13") (pintype "tri_state"))
      (node (ref "TFT") (pin "17") (pinfunction "17_17") (pintype "passive"))
    )
    (net (code "63") (name "/DB11") (class "Default")
      (node (ref "IC2") (pin "15") (pinfunction "Y4_15") (pintype "tri_state"))
      (node (ref "TFT") (pin "19") (pinfunction "19_19") (pintype "passive"))
    )
    (net (code "64") (name "/DB12") (class "Default")
      (node (ref "IC2") (pin "17") (pinfunction "Y2_17") (pintype "tri_state"))
      (node (ref "TFT") (pin "21") (pinfunction "21_21") (pintype "passive"))
    )
    (net (code "65") (name "/DB13") (class "Default")
      (node (ref "IC3") (pin "18") (pinfunction "Y1_18") (pintype "tri_state"))
      (node (ref "TFT") (pin "23") (pinfunction "23_23") (pintype "passive"))
    )
    (net (code "66") (name "/DB14") (class "Default")
      (node (ref "IC3") (pin "17") (pinfunction "Y2_17") (pintype "tri_state"))
      (node (ref "TFT") (pin "25") (pinfunction "25_25") (pintype "passive"))
    )
    (net (code "67") (name "/DB15") (class "Default")
      (node (ref "IC3") (pin "12") (pinfunction "Y7_12") (pintype "tri_state"))
      (node (ref "TFT") (pin "27") (pinfunction "27_27") (pintype "passive"))
    )
    (net (code "68") (name "/D_CLK") (class "Default")
      (node (ref "IC2") (pin "14") (pinfunction "Y5_14") (pintype "tri_state"))
      (node (ref "TFT") (pin "18") (pinfunction "18_18") (pintype "passive"))
    )
    (net (code "69") (name "/D_CS") (class "Default")
      (node (ref "IC2") (pin "16") (pinfunction "Y3_16") (pintype "tri_state"))
      (node (ref "TFT") (pin "20") (pinfunction "20_20") (pintype "passive"))
    )
    (net (code "70") (name "/D_DIN") (class "Default")
      (node (ref "IC2") (pin "18") (pinfunction "Y1_18") (pintype "tri_state"))
      (node (ref "TFT") (pin "22") (pinfunction "22_22") (pintype "passive"))
    )
    (net (code "71") (name "/D_OUT") (class "Default")
      (node (ref "IC5") (pin "3") (pinfunction "A2_3") (pintype "input"))
      (node (ref "TFT") (pin "26") (pinfunction "26_26") (pintype "passive"))
    )
    (net (code "72") (name "/D_PENIRQ") (class "Default")
      (node (ref "IC5") (pin "16") (pinfunction "Y3_16") (pintype "tri_state"))
      (node (ref "U1") (pin "D2") (pinfunction "*D2_D2") (pintype "bidirectional"))
    )
    (net (code "73") (name "/D_PENIRQ_TFT") (class "Default")
      (node (ref "IC5") (pin "4") (pinfunction "A3_4") (pintype "input"))
      (node (ref "TFT") (pin "28") (pinfunction "28_28") (pintype "passive"))
    )
    (net (code "74") (name "/LED") (class "Default")
      (node (ref "RN1") (pin "8") (pinfunction "2_8") (pintype "passive"))
      (node (ref "U1") (pin "D13") (pinfunction "D13_D13") (pintype "bidirectional"))
    )
    (net (code "75") (name "/RESET") (class "Default")
      (node (ref "S2") (pin "3") (pinfunction "3_3") (pintype "passive"))
      (node (ref "S2") (pin "4") (pinfunction "4_4") (pintype "passive"))
      (node (ref "U1") (pin "RES") (pinfunction "RES_RES") (pintype "bidirectional"))
    )
    (net (code "76") (name "/SCL") (class "Default")
      (node (ref "JP3") (pin "2") (pinfunction "2_2") (pintype "passive"))
      (node (ref "U1") (pin "D21") (pinfunction "*D21_D21") (pintype "bidirectional"))
    )
    (net (code "77") (name "/SDA") (class "Default")
      (node (ref "JP3") (pin "1") (pinfunction "1_1") (pintype "passive"))
      (node (ref "U1") (pin "D20") (pinfunction "*D20_D20") (pintype "bidirectional"))
    )
    (net (code "78") (name "/SERV1") (class "Default")
      (node (ref "SER1") (pin "3") (pinfunction "3_3") (pintype "passive"))
      (node (ref "U1") (pin "D9") (pinfunction "D9_D9") (pintype "bidirectional"))
    )
    (net (code "79") (name "/SERV2") (class "Default")
      (node (ref "SER2") (pin "3") (pinfunction "3_3") (pintype "passive"))
      (node (ref "U1") (pin "D10") (pinfunction "D10_D10") (pintype "bidirectional"))
    )
    (net (code "80") (name "/SPI_MISO") (class "Default")
      (node (ref "IC5") (pin "15") (pinfunction "Y4_15") (pintype "tri_state"))
      (node (ref "U1") (pin "D50") (pinfunction "D50_D50") (pintype "bidirectional"))
    )
    (net (code "81") (name "/SPI_MISO_TFT") (class "Default")
      (node (ref "IC5") (pin "5") (pinfunction "A4_5") (pintype "input"))
      (node (ref "TFT") (pin "30") (pinfunction "30_30") (pintype "passive"))
    )
    (net (code "82") (name "/SPI_MOSI") (class "Default")
      (node (ref "IC4") (pin "6") (pinfunction "A5_6") (pintype "input"))
      (node (ref "U1") (pin "D51") (pinfunction "D51_D51") (pintype "bidirectional"))
    )
    (net (code "83") (name "/SPI_MOSI_TFT") (class "Default")
      (node (ref "IC4") (pin "14") (pinfunction "Y5_14") (pintype "tri_state"))
      (node (ref "TFT") (pin "34") (pinfunction "34_34") (pintype "passive"))
    )
    (net (code "84") (name "/SPI_SCK") (class "Default")
      (node (ref "IC4") (pin "4") (pinfunction "A3_4") (pintype "input"))
      (node (ref "U1") (pin "D52") (pinfunction "D52_D52") (pintype "bidirectional"))
    )
    (net (code "85") (name "/SPI_SCK_TFT") (class "Default")
      (node (ref "IC4") (pin "16") (pinfunction "Y3_16") (pintype "tri_state"))
      (node (ref "TFT") (pin "32") (pinfunction "32_32") (pintype "passive"))
    )
    (net (code "86") (name "/SPI_SS") (class "Default")
      (node (ref "IC4") (pin "5") (pinfunction "A4_5") (pintype "input"))
      (node (ref "U1") (pin "D53") (pinfunction "D53_D53") (pintype "bidirectional"))
    )
    (net (code "87") (name "/SPI_SS_TFT") (class "Default")
      (node (ref "IC4") (pin "15") (pinfunction "Y4_15") (pintype "tri_state"))
      (node (ref "TFT") (pin "36") (pinfunction "36_36") (pintype "passive"))
    )
    (net (code "88") (name "/TFT_CS") (class "Default")
      (node (ref "IC4") (pin "17") (pinfunction "Y2_17") (pintype "tri_state"))
      (node (ref "TFT") (pin "29") (pinfunction "29_29") (pintype "passive"))
    )
    (net (code "89") (name "/TFT_LEDA") (class "Default")
      (node (ref "R26") (pin "2") (pinfunction "2_2") (pintype "passive"))
      (node (ref "TFT") (pin "37") (pinfunction "37_37") (pintype "passive"))
    )
    (net (code "90") (name "/TFT_RD") (class "Default")
      (node (ref "R13") (pin "2") (pinfunction "2_2") (pintype "passive"))
      (node (ref "TFT") (pin "11") (pinfunction "11_11") (pintype "passive"))
    )
    (net (code "91") (name "/TFT_REST") (class "Default")
      (node (ref "IC4") (pin "13") (pinfunction "Y6_13") (pintype "tri_state"))
      (node (ref "TFT") (pin "33") (pinfunction "33_33") (pintype "passive"))
    )
    (net (code "92") (name "/TFT_RS") (class "Default")
      (node (ref "IC4") (pin "18") (pinfunction "Y1_18") (pintype "tri_state"))
      (node (ref "TFT") (pin "7") (pinfunction "7_7") (pintype "passive"))
    )
    (net (code "93") (name "/TFT_WR") (class "Default")
      (node (ref "IC4") (pin "12") (pinfunction "Y7_12") (pintype "tri_state"))
      (node (ref "TFT") (pin "9") (pinfunction "9_9") (pintype "passive"))
    )
    (net (code "94") (name "/VIN") (class "Default")
      (node (ref "U1") (pin "VIN") (pinfunction "VIN_VIN") (pintype "bidirectional"))
    )
    (net (code "95") (name "/X-MAX") (class "Default")
      (node (ref "U1") (pin "D17") (pinfunction "D17_D17") (pintype "bidirectional"))
      (node (ref "X-MAX") (pin "3") (pinfunction "3_3") (pintype "passive"))
    )
    (net (code "96") (name "/X-MIN") (class "Default")
      (node (ref "U1") (pin "D16") (pinfunction "D16_D16") (pintype "bidirectional"))
      (node (ref "X-MIN") (pin "3") (pinfunction "3_3") (pintype "passive"))
    )
    (net (code "97") (name "/Y-MAX") (class "Default")
      (node (ref "U1") (pin "D15") (pinfunction "D15_D15") (pintype "bidirectional"))
      (node (ref "Y-MAX") (pin "3") (pinfunction "3_3") (pintype "passive"))
    )
    (net (code "98") (name "/Y-MIN") (class "Default")
      (node (ref "U1") (pin "D14") (pinfunction "D14_D14") (pintype "bidirectional"))
      (node (ref "Y-MIN") (pin "3") (pinfunction "3_3") (pintype "passive"))
    )
    (net (code "99") (name "GND") (class "Default")
      (node (ref "A_STP") (pin "C") (pinfunction "C_C") (pintype "passive"))
      (node (ref "B_STP") (pin "C") (pinfunction "C_C") (pintype "passive"))
      (node (ref "C1") (pin "-") (pinfunction "-_-") (pintype "passive"))
      (node (ref "C10") (pin "1") (pinfunction "1_1") (pintype "passive"))
      (node (ref "C11") (pin "-") (pinfunction "-_-") (pintype "passive"))
      (node (ref "C12") (pin "-") (pinfunction "-_-") (pintype "passive"))
      (node (ref "C13") (pin "1") (pinfunction "1_1") (pintype "passive"))
      (node (ref "C14") (pin "1") (pinfunction "1_1") (pintype "passive"))
      (node (ref "C3") (pin "-") (pinfunction "-_-") (pintype "passive"))
      (node (ref "C4") (pin "-") (pinfunction "-_-") (pintype "passive"))
      (node (ref "C6") (pin "1") (pinfunction "1_1") (pintype "passive"))
      (node (ref "C7") (pin "2") (pinfunction "2_2") (pintype "passive"))
      (node (ref "C9") (pin "2") (pinfunction "2_2") (pintype "passive"))
      (node (ref "C_STP") (pin "C") (pinfunction "C_C") (pintype "passive"))
      (node (ref "D13") (pin "C") (pinfunction "C_C") (pintype "passive"))
      (node (ref "IC1") (pin "GND") (pinfunction "GND_GND") (pintype "bidirectional"))
      (node (ref "IC1") (pin "GND1") (pinfunction "GND1_GND1") (pintype "bidirectional"))
      (node (ref "IC2") (pin "1") (pinfunction "G1_1") (pintype "input"))
      (node (ref "IC2") (pin "10") (pinfunction "GND_10") (pintype "power_in"))
      (node (ref "IC2") (pin "19") (pinfunction "G2_19") (pintype "input"))
      (node (ref "IC3") (pin "1") (pinfunction "G1_1") (pintype "input"))
      (node (ref "IC3") (pin "10") (pinfunction "GND_10") (pintype "power_in"))
      (node (ref "IC3") (pin "19") (pinfunction "G2_19") (pintype "input"))
      (node (ref "IC3") (pin "4") (pinfunction "A3_4") (pintype "input"))
      (node (ref "IC3") (pin "5") (pinfunction "A4_5") (pintype "input"))
      (node (ref "IC3") (pin "6") (pinfunction "A5_6") (pintype "input"))
      (node (ref "IC3") (pin "7") (pinfunction "A6_7") (pintype "input"))
      (node (ref "IC3") (pin "9") (pinfunction "A8_9") (pintype "input"))
      (node (ref "IC4") (pin "1") (pinfunction "G1_1") (pintype "input"))
      (node (ref "IC4") (pin "10") (pinfunction "GND_10") (pintype "power_in"))
      (node (ref "IC4") (pin "19") (pinfunction "G2_19") (pintype "input"))
      (node (ref "IC4") (pin "9") (pinfunction "A8_9") (pintype "input"))
      (node (ref "IC5") (pin "1") (pinfunction "G1_1") (pintype "input"))
      (node (ref "IC5") (pin "10") (pinfunction "GND_10") (pintype "power_in"))
      (node (ref "IC5") (pin "19") (pinfunction "G2_19") (pintype "input"))
      (node (ref "IC5") (pin "2") (pinfunction "A1_2") (pintype "input"))
      (node (ref "IC5") (pin "6") (pinfunction "A5_6") (pintype "input"))
      (node (ref "IC5") (pin "7") (pinfunction "A6_7") (pintype "input"))
      (node (ref "IC5") (pin "8") (pinfunction "A7_8") (pintype "input"))
      (node (ref "IC5") (pin "9") (pinfunction "A8_9") (pintype "input"))
      (node (ref "J1") (pin "2") (pinfunction "2_2") (pintype "passive"))
      (node (ref "JP8") (pin "GND") (pinfunction "GND_GND") (pintype "bidirectional"))
      (node (ref "JP8") (pin "GNDBREAK") (pinfunction "GNDBREAK_GNDBREAK") (pintype "bidirectional"))
      (node (ref "PWR") (pin "C") (pinfunction "C_C") (pintype "passive"))
      (node (ref "PWR1") (pin "C") (pinfunction "C_C") (pintype "passive"))
      (node (ref "R1") (pin "2") (pinfunction "2_2") (pintype "passive"))
      (node (ref "R10") (pin "1") (pinfunction "1_1") (pintype "passive"))
      (node (ref "R5") (pin "2") (pinfunction "2_2") (pintype "passive"))
      (node (ref "R7") (pin "1") (pinfunction "1_1") (pintype "passive"))
      (node (ref "R8") (pin "2") (pinfunction "2_2") (pintype "passive"))
      (node (ref "S2") (pin "1") (pinfunction "1_1") (pintype "passive"))
      (node (ref "S2") (pin "2") (pinfunction "2_2") (pintype "passive"))
      (node (ref "SER1") (pin "1") (pinfunction "1_1") (pintype "passive"))
      (node (ref "SER2") (pin "1") (pinfunction "1_1") (pintype "passive"))
      (node (ref "TFT") (pin "1") (pinfunction "1_1") (pintype "passive"))
      (node (ref "TFT") (pin "10") (pinfunction "10_10") (pintype "passive"))
      (node (ref "TFT") (pin "12") (pinfunction "12_12") (pintype "passive"))
      (node (ref "TFT") (pin "14") (pinfunction "14_14") (pintype "passive"))
      (node (ref "TFT") (pin "16") (pinfunction "16_16") (pintype "passive"))
      (node (ref "TFT") (pin "2") (pinfunction "2_2") (pintype "passive"))
      (node (ref "TFT") (pin "4") (pinfunction "4_4") (pintype "passive"))
      (node (ref "TFT") (pin "6") (pinfunction "6_6") (pintype "passive"))
      (node (ref "TFT") (pin "8") (pinfunction "8_8") (pintype "passive"))
      (node (ref "U$1") (pin "GND") (pinfunction "GND_GND") (pintype "power_in"))
      (node (ref "U$1") (pin "GND@0") (pinfunction "GND_GND@0") (pintype "power_in"))
      (node (ref "U$6") (pin "GND") (pinfunction "GND_GND") (pintype "power_in"))
      (node (ref "U$6") (pin "GND@0") (pinfunction "GND_GND@0") (pintype "power_in"))
      (node (ref "U$7") (pin "GND") (pinfunction "GND_GND") (pintype "power_in"))
      (node (ref "U$7") (pin "GND@0") (pinfunction "GND_GND@0") (pintype "power_in"))
      (node (ref "U1") (pin "GND@0") (pinfunction "GND_GND@0") (pintype "power_in"))
      (node (ref "U1") (pin "GND@1") (pinfunction "GND_GND@1") (pintype "power_in"))
      (node (ref "U1") (pin "GND@2") (pinfunction "GND_GND@2") (pintype "power_in"))
      (node (ref "U1") (pin "GND@3") (pinfunction "GND_GND@3") (pintype "power_in"))
      (node (ref "U1") (pin "GND@4") (pinfunction "GND_GND@4") (pintype "power_in"))
      (node (ref "X-MAX") (pin "1") (pinfunction "1_1") (pintype "passive"))
      (node (ref "X-MIN") (pin "1") (pinfunction "1_1") (pintype "passive"))
      (node (ref "Y-MAX") (pin "1") (pinfunction "1_1") (pintype "passive"))
      (node (ref "Y-MIN") (pin "1") (pinfunction "1_1") (pintype "passive"))
    )
    (net (code "100") (name "Net-(A-MOT1-Pad1)") (class "Default")
      (node (ref "A-MOT1") (pin "1") (pinfunction "1_1") (pintype "bidirectional"))
      (node (ref "A-MOT2") (pin "1") (pinfunction "1_1") (pintype "passive"))
      (node (ref "U$1") (pin "2B") (pinfunction "2B_2B") (pintype "output"))
    )
    (net (code "101") (name "Net-(A-MOT1-Pad2)") (class "Default")
      (node (ref "A-MOT1") (pin "2") (pinfunction "2_2") (pintype "bidirectional"))
      (node (ref "A-MOT2") (pin "2") (pinfunction "2_2") (pintype "passive"))
      (node (ref "U$1") (pin "2A") (pinfunction "2A_2A") (pintype "output"))
    )
    (net (code "102") (name "Net-(A-MOT1-Pad3)") (class "Default")
      (node (ref "A-MOT1") (pin "3") (pinfunction "3_3") (pintype "bidirectional"))
      (node (ref "A-MOT2") (pin "3") (pinfunction "3_3") (pintype "passive"))
      (node (ref "U$1") (pin "1A") (pinfunction "1A_1A") (pintype "output"))
    )
    (net (code "103") (name "Net-(A-MOT1-Pad4)") (class "Default")
      (node (ref "A-MOT1") (pin "4") (pinfunction "4_4") (pintype "bidirectional"))
      (node (ref "A-MOT2") (pin "4") (pinfunction "4_4") (pintype "passive"))
      (node (ref "U$1") (pin "1B") (pinfunction "1B_1B") (pintype "output"))
    )
    (net (code "104") (name "Net-(A_STP-PadA)") (class "Default")
      (node (ref "A_STP") (pin "A") (pinfunction "A_A") (pintype "passive"))
      (node (ref "R6") (pin "1") (pinfunction "1_1") (pintype "passive"))
    )
    (net (code "105") (name "Net-(B-MOT1-Pad1)") (class "Default")
      (node (ref "B-MOT1") (pin "1") (pinfunction "1_1") (pintype "bidirectional"))
      (node (ref "B-MOT2") (pin "1") (pinfunction "1_1") (pintype "passive"))
      (node (ref "U$7") (pin "2B") (pinfunction "2B_2B") (pintype "output"))
    )
    (net (code "106") (name "Net-(B-MOT1-Pad2)") (class "Default")
      (node (ref "B-MOT1") (pin "2") (pinfunction "2_2") (pintype "bidirectional"))
      (node (ref "B-MOT2") (pin "2") (pinfunction "2_2") (pintype "passive"))
      (node (ref "U$7") (pin "2A") (pinfunction "2A_2A") (pintype "output"))
    )
    (net (code "107") (name "Net-(B-MOT1-Pad3)") (class "Default")
      (node (ref "B-MOT1") (pin "3") (pinfunction "3_3") (pintype "bidirectional"))
      (node (ref "B-MOT2") (pin "3") (pinfunction "3_3") (pintype "passive"))
      (node (ref "U$7") (pin "1A") (pinfunction "1A_1A") (pintype "output"))
    )
    (net (code "108") (name "Net-(B-MOT1-Pad4)") (class "Default")
      (node (ref "B-MOT1") (pin "4") (pinfunction "4_4") (pintype "bidirectional"))
      (node (ref "B-MOT2") (pin "4") (pinfunction "4_4") (pintype "passive"))
      (node (ref "U$7") (pin "1B") (pinfunction "1B_1B") (pintype "output"))
    )
    (net (code "109") (name "Net-(B_STP-PadA)") (class "Default")
      (node (ref "B_STP") (pin "A") (pinfunction "A_A") (pintype "passive"))
      (node (ref "R11") (pin "1") (pinfunction "1_1") (pintype "passive"))
    )
    (net (code "110") (name "Net-(C-MOT1-Pad1)") (class "Default")
      (node (ref "C-MOT1") (pin "1") (pinfunction "1_1") (pintype "bidirectional"))
      (node (ref "C-MOT2") (pin "1") (pinfunction "1_1") (pintype "passive"))
      (node (ref "U$6") (pin "2B") (pinfunction "2B_2B") (pintype "output"))
    )
    (net (code "111") (name "Net-(C-MOT1-Pad2)") (class "Default")
      (node (ref "C-MOT1") (pin "2") (pinfunction "2_2") (pintype "bidirectional"))
      (node (ref "C-MOT2") (pin "2") (pinfunction "2_2") (pintype "passive"))
      (node (ref "U$6") (pin "2A") (pinfunction "2A_2A") (pintype "output"))
    )
    (net (code "112") (name "Net-(C-MOT1-Pad3)") (class "Default")
      (node (ref "C-MOT1") (pin "3") (pinfunction "3_3") (pintype "bidirectional"))
      (node (ref "C-MOT2") (pin "3") (pinfunction "3_3") (pintype "passive"))
      (node (ref "U$6") (pin "1A") (pinfunction "1A_1A") (pintype "output"))
    )
    (net (code "113") (name "Net-(C-MOT1-Pad4)") (class "Default")
      (node (ref "C-MOT1") (pin "4") (pinfunction "4_4") (pintype "bidirectional"))
      (node (ref "C-MOT2") (pin "4") (pinfunction "4_4") (pintype "passive"))
      (node (ref "U$6") (pin "1B") (pinfunction "1B_1B") (pintype "output"))
    )
    (net (code "114") (name "Net-(C5-Pad1)") (class "Default")
      (node (ref "C5") (pin "1") (pinfunction "1_1") (pintype "passive"))
      (node (ref "IC1") (pin "COMP") (pinfunction "COMP_COMP") (pintype "bidirectional"))
    )
    (net (code "115") (name "Net-(C5-Pad2)") (class "Default")
      (node (ref "C5") (pin "2") (pinfunction "2_2") (pintype "passive"))
      (node (ref "R7") (pin "2") (pinfunction "2_2") (pintype "passive"))
    )
    (net (code "116") (name "Net-(C8-Pad1)") (class "Default")
      (node (ref "C8") (pin "1") (pinfunction "1_1") (pintype "passive"))
      (node (ref "IC1") (pin "BS") (pinfunction "BS_BS") (pintype "bidirectional"))
    )
    (net (code "117") (name "Net-(C8-Pad2)") (class "Default")
      (node (ref "C8") (pin "2") (pinfunction "2_2") (pintype "passive"))
      (node (ref "IC1") (pin "SW") (pinfunction "SW_SW") (pintype "bidirectional"))
      (node (ref "L1") (pin "1") (pinfunction "1_1") (pintype "passive"))
    )
    (net (code "118") (name "Net-(C9-Pad1)") (class "Default")
      (node (ref "C9") (pin "1") (pinfunction "1_1") (pintype "passive"))
      (node (ref "IC1") (pin "SS") (pinfunction "SS_SS") (pintype "bidirectional"))
    )
    (net (code "119") (name "Net-(C12-Pad+)") (class "Default")
      (node (ref "C12") (pin "+") (pinfunction "+_+") (pintype "passive"))
      (node (ref "C7") (pin "1") (pinfunction "1_1") (pintype "passive"))
      (node (ref "D2") (pin "A") (pinfunction "A_A") (pintype "passive"))
      (node (ref "L1") (pin "2") (pinfunction "2_2") (pintype "passive"))
      (node (ref "ON_BOARD_PWR") (pin "1") (pinfunction "1_1") (pintype "passive"))
      (node (ref "ON_BOARD_PWR") (pin "2") (pinfunction "2_2") (pintype "passive"))
      (node (ref "R12") (pin "1") (pinfunction "1_1") (pintype "passive"))
      (node (ref "R9") (pin "2") (pinfunction "2_2") (pintype "passive"))
    )
    (net (code "120") (name "Net-(C_STP-PadA)") (class "Default")
      (node (ref "C_STP") (pin "A") (pinfunction "A_A") (pintype "passive"))
      (node (ref "R3") (pin "1") (pinfunction "1_1") (pintype "passive"))
    )
    (net (code "121") (name "Net-(D13-PadA)") (class "Default")
      (node (ref "D13") (pin "A") (pinfunction "A_A") (pintype "passive"))
      (node (ref "RN1") (pin "1") (pinfunction "1_1") (pintype "passive"))
    )
    (net (code "122") (name "Net-(IC1-PadEN)") (class "Default")
      (node (ref "IC1") (pin "EN") (pinfunction "EN_EN") (pintype "bidirectional"))
      (node (ref "R4") (pin "2") (pinfunction "2_2") (pintype "passive"))
    )
    (net (code "123") (name "Net-(IC1-PadFB)") (class "Default")
      (node (ref "IC1") (pin "FB") (pinfunction "FB_FB") (pintype "bidirectional"))
      (node (ref "R10") (pin "2") (pinfunction "2_2") (pintype "passive"))
      (node (ref "R9") (pin "1") (pinfunction "1_1") (pintype "passive"))
    )
    (net (code "124") (name "Net-(PWR1-PadA)") (class "Default")
      (node (ref "PWR1") (pin "A") (pinfunction "A_A") (pintype "passive"))
      (node (ref "R12") (pin "2") (pinfunction "2_2") (pintype "passive"))
    )
    (net (code "125") (name "Net-(R1-Pad1)") (class "Default")
      (node (ref "R1") (pin "1") (pinfunction "1_1") (pintype "passive"))
      (node (ref "SJ7") (pin "2") (pinfunction "2_2") (pintype "passive"))
      (node (ref "U$1") (pin "MS1") (pinfunction "MS1_MS1") (pintype "input"))
    )
    (net (code "126") (name "Net-(R5-Pad1)") (class "Default")
      (node (ref "R5") (pin "1") (pinfunction "1_1") (pintype "passive"))
      (node (ref "SJ1") (pin "2") (pinfunction "2_2") (pintype "passive"))
      (node (ref "U$6") (pin "MS1") (pinfunction "MS1_MS1") (pintype "input"))
    )
    (net (code "127") (name "Net-(R8-Pad1)") (class "Default")
      (node (ref "R8") (pin "1") (pinfunction "1_1") (pintype "passive"))
      (node (ref "SJ3") (pin "2") (pinfunction "2_2") (pintype "passive"))
      (node (ref "U$7") (pin "MS1") (pinfunction "MS1_MS1") (pintype "input"))
    )
    (net (code "128") (name "Net-(RN1B-1)") (class "Default")
      (node (ref "RN1") (pin "2") (pinfunction "1_2") (pintype "passive"))
      (node (ref "RX_LED") (pin "C") (pinfunction "C_C") (pintype "passive"))
    )
    (net (code "129") (name "Net-(RN1C-1)") (class "Default")
      (node (ref "RN1") (pin "3") (pinfunction "1_3") (pintype "passive"))
      (node (ref "TX_LED") (pin "C") (pinfunction "C_C") (pintype "passive"))
    )
    (net (code "130") (name "Net-(RN1D-1)") (class "Default")
      (node (ref "PWR") (pin "A") (pinfunction "A_A") (pintype "passive"))
      (node (ref "RN1") (pin "4") (pinfunction "1_4") (pintype "passive"))
    )
    (net (code "131") (name "Net-(SJ2-Pad2)") (class "Default")
      (node (ref "SJ2") (pin "2") (pinfunction "2_2") (pintype "passive"))
      (node (ref "U$6") (pin "MS2") (pinfunction "MS2_MS2") (pintype "input"))
    )
    (net (code "132") (name "Net-(SJ4-Pad2)") (class "Default")
      (node (ref "SJ4") (pin "2") (pinfunction "2_2") (pintype "passive"))
      (node (ref "U$7") (pin "MS2") (pinfunction "MS2_MS2") (pintype "input"))
    )
    (net (code "133") (name "Net-(SJ5-Pad2)") (class "Default")
      (node (ref "SJ5") (pin "2") (pinfunction "2_2") (pintype "passive"))
      (node (ref "U$6") (pin "MS3") (pinfunction "MS3_MS3") (pintype "input"))
    )
    (net (code "134") (name "Net-(SJ6-Pad2)") (class "Default")
      (node (ref "SJ6") (pin "2") (pinfunction "2_2") (pintype "passive"))
      (node (ref "U$7") (pin "MS3") (pinfunction "MS3_MS3") (pintype "input"))
    )
    (net (code "135") (name "Net-(SJ8-Pad2)") (class "Default")
      (node (ref "SJ8") (pin "2") (pinfunction "2_2") (pintype "passive"))
      (node (ref "U$1") (pin "MS2") (pinfunction "MS2_MS2") (pintype "input"))
    )
    (net (code "136") (name "Net-(SJ9-Pad2)") (class "Default")
      (node (ref "SJ9") (pin "2") (pinfunction "2_2") (pintype "passive"))
      (node (ref "U$1") (pin "MS3") (pinfunction "MS3_MS3") (pintype "input"))
    )
    (net (code "137") (name "Net-(U$1-SLEEP)") (class "Default")
      (node (ref "U$1") (pin "RST") (pinfunction "RST_RST") (pintype "input"))
      (node (ref "U$1") (pin "SLP") (pinfunction "SLEEP_SLP") (pintype "input"))
    )
    (net (code "138") (name "Net-(U$6-SLEEP)") (class "Default")
      (node (ref "U$6") (pin "RST") (pinfunction "RST_RST") (pintype "input"))
      (node (ref "U$6") (pin "SLP") (pinfunction "SLEEP_SLP") (pintype "input"))
    )
    (net (code "139") (name "Net-(U$7-SLEEP)") (class "Default")
      (node (ref "U$7") (pin "RST") (pinfunction "RST_RST") (pintype "input"))
      (node (ref "U$7") (pin "SLP") (pinfunction "SLEEP_SLP") (pintype "input"))
    )
    (net (code "140") (name "VCC") (class "Default")
      (node (ref "D2") (pin "C") (pinfunction "C_C") (pintype "passive"))
      (node (ref "IC5") (pin "20") (pinfunction "VCC_20") (pintype "power_in"))
      (node (ref "R18") (pin "1") (pinfunction "1_1") (pintype "passive"))
      (node (ref "R19") (pin "1") (pinfunction "1_1") (pintype "passive"))
      (node (ref "R2") (pin "1") (pinfunction "1_1") (pintype "passive"))
      (node (ref "RN1") (pin "5") (pinfunction "2_5") (pintype "passive"))
      (node (ref "RX_LED") (pin "A") (pinfunction "A_A") (pintype "passive"))
      (node (ref "SER1") (pin "2") (pinfunction "2_2") (pintype "passive"))
      (node (ref "SER2") (pin "2") (pinfunction "2_2") (pintype "passive"))
      (node (ref "SJ1") (pin "1") (pinfunction "1_1") (pintype "passive"))
      (node (ref "SJ2") (pin "1") (pinfunction "1_1") (pintype "passive"))
      (node (ref "SJ3") (pin "1") (pinfunction "1_1") (pintype "passive"))
      (node (ref "SJ4") (pin "1") (pinfunction "1_1") (pintype "passive"))
      (node (ref "SJ5") (pin "1") (pinfunction "1_1") (pintype "passive"))
      (node (ref "SJ6") (pin "1") (pinfunction "1_1") (pintype "passive"))
      (node (ref "SJ7") (pin "1") (pinfunction "1_1") (pintype "passive"))
      (node (ref "SJ8") (pin "1") (pinfunction "1_1") (pintype "passive"))
      (node (ref "SJ9") (pin "1") (pinfunction "1_1") (pintype "passive"))
      (node (ref "TFT") (pin "3") (pinfunction "3_3") (pintype "passive"))
      (node (ref "TX_LED") (pin "A") (pinfunction "A_A") (pintype "passive"))
      (node (ref "U$1") (pin "VDD") (pinfunction "VDD_VDD") (pintype "power_in"))
      (node (ref "U$6") (pin "VDD") (pinfunction "VDD_VDD") (pintype "power_in"))
      (node (ref "U$7") (pin "VDD") (pinfunction "VDD_VDD") (pintype "power_in"))
      (node (ref "U1") (pin "5V@0") (pinfunction "5V_5V@0") (pintype "power_in"))
      (node (ref "U1") (pin "5V@1") (pinfunction "5V_5V@1") (pintype "power_in"))
      (node (ref "U1") (pin "5V@2") (pinfunction "5V_5V@2") (pintype "power_in"))
      (node (ref "X-MAX") (pin "2") (pinfunction "2_2") (pintype "passive"))
      (node (ref "X-MIN") (pin "2") (pinfunction "2_2") (pintype "passive"))
      (node (ref "Y-MAX") (pin "2") (pinfunction "2_2") (pintype "passive"))
      (node (ref "Y-MIN") (pin "2") (pinfunction "2_2") (pintype "passive"))
    )
    (net (code "141") (name "unconnected-(IC3A-Y3-Pad16)") (class "Default")
      (node (ref "IC3") (pin "16") (pinfunction "Y3_16") (pintype "tri_state"))
    )
    (net (code "142") (name "unconnected-(IC3A-Y4-Pad15)") (class "Default")
      (node (ref "IC3") (pin "15") (pinfunction "Y4_15") (pintype "tri_state"))
    )
    (net (code "143") (name "unconnected-(IC3A-Y5-Pad14)") (class "Default")
      (node (ref "IC3") (pin "14") (pinfunction "Y5_14") (pintype "tri_state"))
    )
    (net (code "144") (name "unconnected-(IC3A-Y6-Pad13)") (class "Default")
      (node (ref "IC3") (pin "13") (pinfunction "Y6_13") (pintype "tri_state"))
    )
    (net (code "145") (name "unconnected-(IC3A-Y8-Pad11)") (class "Default")
      (node (ref "IC3") (pin "11") (pinfunction "Y8_11") (pintype "tri_state"))
    )
    (net (code "146") (name "unconnected-(IC4A-Y8-Pad11)") (class "Default")
      (node (ref "IC4") (pin "11") (pinfunction "Y8_11") (pintype "tri_state"))
    )
    (net (code "147") (name "unconnected-(IC5A-Y1-Pad18)") (class "Default")
      (node (ref "IC5") (pin "18") (pinfunction "Y1_18") (pintype "tri_state"))
    )
    (net (code "148") (name "unconnected-(IC5A-Y5-Pad14)") (class "Default")
      (node (ref "IC5") (pin "14") (pinfunction "Y5_14") (pintype "tri_state"))
    )
    (net (code "149") (name "unconnected-(IC5A-Y6-Pad13)") (class "Default")
      (node (ref "IC5") (pin "13") (pinfunction "Y6_13") (pintype "tri_state"))
    )
    (net (code "150") (name "unconnected-(IC5A-Y7-Pad12)") (class "Default")
      (node (ref "IC5") (pin "12") (pinfunction "Y7_12") (pintype "tri_state"))
    )
    (net (code "151") (name "unconnected-(IC5A-Y8-Pad11)") (class "Default")
      (node (ref "IC5") (pin "11") (pinfunction "Y8_11") (pintype "tri_state"))
    )
    (net (code "152") (name "unconnected-(TFT-Pad5)") (class "Default")
      (node (ref "TFT") (pin "5") (pinfunction "5_5") (pintype "passive"))
    )
    (net (code "153") (name "unconnected-(TFT-Pad24)") (class "Default")
      (node (ref "TFT") (pin "24") (pinfunction "24_24") (pintype "passive"))
    )
    (net (code "154") (name "unconnected-(TFT-Pad31)") (class "Default")
      (node (ref "TFT") (pin "31") (pinfunction "31_31") (pintype "passive"))
    )
    (net (code "155") (name "unconnected-(TFT-Pad35)") (class "Default")
      (node (ref "TFT") (pin "35") (pinfunction "35_35") (pintype "passive"))
    )
    (net (code "156") (name "unconnected-(TFT-Pad38)") (class "Default")
      (node (ref "TFT") (pin "38") (pinfunction "38_38") (pintype "passive"))
    )
    (net (code "157") (name "unconnected-(TFT-Pad39)") (class "Default")
      (node (ref "TFT") (pin "39") (pinfunction "39_39") (pintype "passive"))
    )
    (net (code "158") (name "unconnected-(TFT-Pad40)") (class "Default")
      (node (ref "TFT") (pin "40") (pinfunction "40_40") (pintype "passive"))
    )
  )
)
